# board1.net
KiCad netlist of a schematic drawn in EAGLE
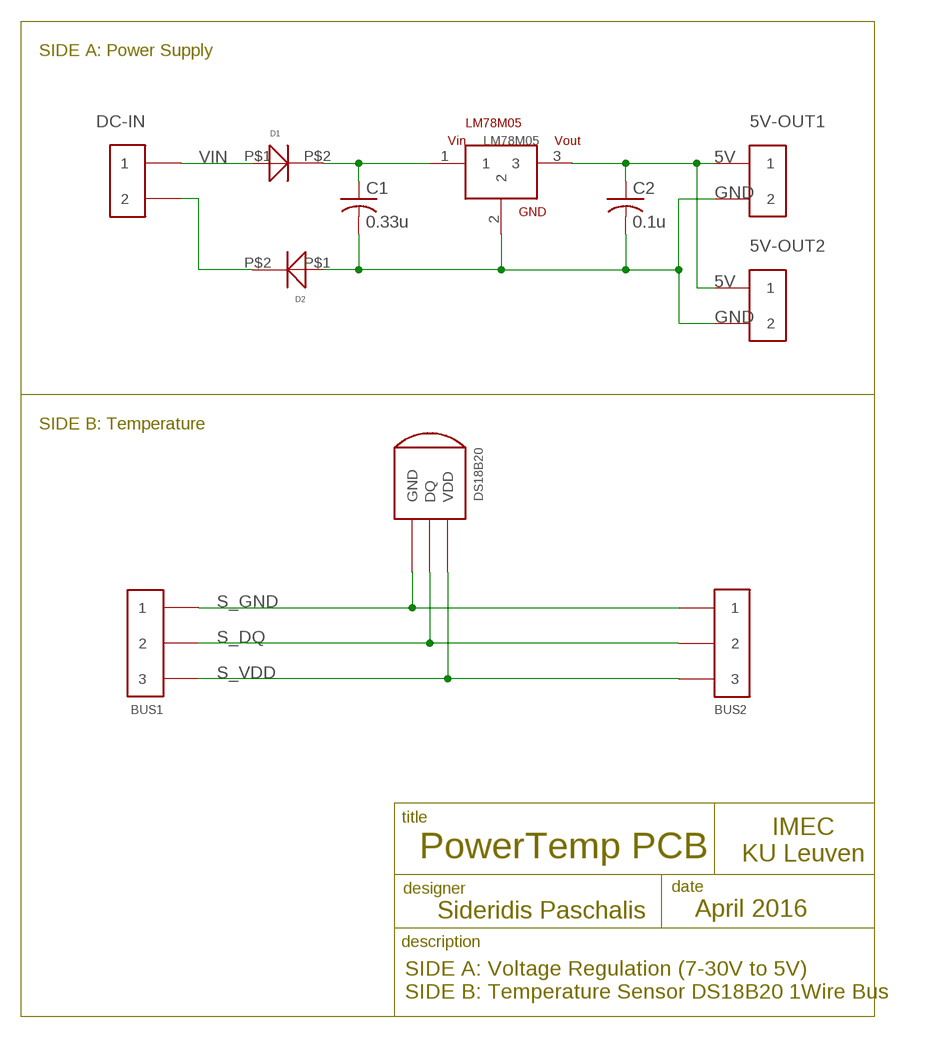
[diagram p0: schematic, sheet 1]

(export (version "E")
  (design (tool "Eeschema 10.0.6"))
  (components
    (comp (ref "5V-OUT1")
      (value "2PIN-TERMINAL-5MMPITCH")
      (footprint "eagle-import:2PIN-TERMINAL-5MMPITCH")
      (libsource (lib "eagle-import") (part "2PIN-TERMINAL-5MMPITCH"))
    )
    (comp (ref "5V-OUT2")
      (value "2PIN-TERMINAL-5MMPITCH")
      (footprint "eagle-import:2PIN-TERMINAL-5MMPITCH")
      (libsource (lib "eagle-import") (part "2PIN-TERMINAL-5MMPITCH"))
    )
    (comp (ref "BUS1")
      (value "AVX-3PIN-SMD-CON")
      (footprint "eagle-import:AVX-3PIN-SMD-CON")
      (libsource (lib "eagle-import") (part "AVX-3PIN-SMD-CON"))
    )
    (comp (ref "BUS2")
      (value "AVX-3PIN-SMD-CON")
      (footprint "eagle-import:AVX-3PIN-SMD-CON")
      (libsource (lib "eagle-import") (part "AVX-3PIN-SMD-CON"))
    )
    (comp (ref "C1")
      (value "0.33u")
      (footprint "eagle-import:C3216")
      (libsource (lib "eagle-import") (part "C-USC3216"))
    )
    (comp (ref "C2")
      (value "0.1u")
      (footprint "eagle-import:C3216")
      (libsource (lib "eagle-import") (part "C-USC3216"))
    )
    (comp (ref "D1")
      (value "DIODE")
      (footprint "eagle-import:DIODE_PAC")
      (libsource (lib "eagle-import") (part "DIODE"))
    )
    (comp (ref "D2")
      (value "DIODE")
      (footprint "eagle-import:DIODE_PAC")
      (libsource (lib "eagle-import") (part "DIODE"))
    )
    (comp (ref "DC-IN")
      (value "2PIN-TERMINAL-5MMPITCH")
      (footprint "eagle-import:2PIN-TERMINAL-5MMPITCH")
      (libsource (lib "eagle-import") (part "2PIN-TERMINAL-5MMPITCH"))
    )
    (comp (ref "DS18B20")
      (value "SMD-3PAD-DS18B20")
      (footprint "eagle-import:SMD-3PAD-DS18B20")
      (libsource (lib "eagle-import") (part "SMD-3PAD-DS18B20"))
    )
    (comp (ref "LM78M05")
      (value "LM78M05")
      (footprint "eagle-import:LM78M05_PAC")
      (libsource (lib "eagle-import") (part "LM78M05"))
    )
  )
  (nets
    (net (code "1") (name "/5V") (class "Default")
      (node (ref "5V-OUT1") (pin "1") (pinfunction "1_1") (pintype "bidirectional"))
      (node (ref "5V-OUT2") (pin "1") (pinfunction "1_1") (pintype "bidirectional"))
      (node (ref "C2") (pin "1") (pinfunction "1_1") (pintype "passive"))
      (node (ref "LM78M05") (pin "3") (pinfunction "3_3") (pintype "bidirectional"))
    )
    (net (code "2") (name "/GND") (class "Default")
      (node (ref "5V-OUT1") (pin "2") (pinfunction "2_2") (pintype "bidirectional"))
      (node (ref "5V-OUT2") (pin "2") (pinfunction "2_2") (pintype "bidirectional"))
      (node (ref "C1") (pin "2") (pinfunction "2_2") (pintype "passive"))
      (node (ref "C2") (pin "2") (pinfunction "2_2") (pintype "passive"))
      (node (ref "D2") (pin "P$1") (pinfunction "1_P$1") (pintype "bidirectional"))
      (node (ref "LM78M05") (pin "2") (pinfunction "2_2") (pintype "bidirectional"))
    )
    (net (code "3") (name "/S_DQ") (class "Default")
      (node (ref "BUS1") (pin "P$2") (pinfunction "2_P$2") (pintype "bidirectional"))
      (node (ref "BUS2") (pin "P$2") (pinfunction "2_P$2") (pintype "bidirectional"))
      (node (ref "DS18B20") (pin "P$2") (pinfunction "DQ_P$2") (pintype "bidirectional"))
    )
    (net (code "4") (name "/S_GND") (class "Default")
      (node (ref "BUS1") (pin "P$1") (pinfunction "1_P$1") (pintype "bidirectional"))
      (node (ref "BUS2") (pin "P$1") (pinfunction "1_P$1") (pintype "bidirectional"))
      (node (ref "DS18B20") (pin "P$1") (pinfunction "GND_P$1") (pintype "bidirectional"))
    )
    (net (code "5") (name "/S_VDD") (class "Default")
      (node (ref "BUS1") (pin "P$3") (pinfunction "3_P$3") (pintype "bidirectional"))
      (node (ref "BUS2") (pin "P$3") (pinfunction "3_P$3") (pintype "bidirectional"))
      (node (ref "DS18B20") (pin "P$3") (pinfunction "VDD_P$3") (pintype "bidirectional"))
    )
    (net (code "6") (name "/VIN") (class "Default")
      (node (ref "D1") (pin "P$1") (pinfunction "1_P$1") (pintype "bidirectional"))
      (node (ref "DC-IN") (pin "1") (pinfunction "1_1") (pintype "bidirectional"))
    )
    (net (code "7") (name "Net-(D1-2)") (class "Default")
      (node (ref "C1") (pin "1") (pinfunction "1_1") (pintype "passive"))
      (node (ref "D1") (pin "P$2") (pinfunction "2_P$2") (pintype "bidirectional"))
      (node (ref "LM78M05") (pin "1") (pinfunction "1_1") (pintype "bidirectional"))
    )
    (net (code "8") (name "Net-(D2-2)") (class "Default")
      (node (ref "D2") (pin "P$2") (pinfunction "2_P$2") (pintype "bidirectional"))
      (node (ref "DC-IN") (pin "2") (pinfunction "2_2") (pintype "bidirectional"))
    )
  )
)
